# DSO_Front.net
KiCad netlist of a schematic drawn in Altium Designer
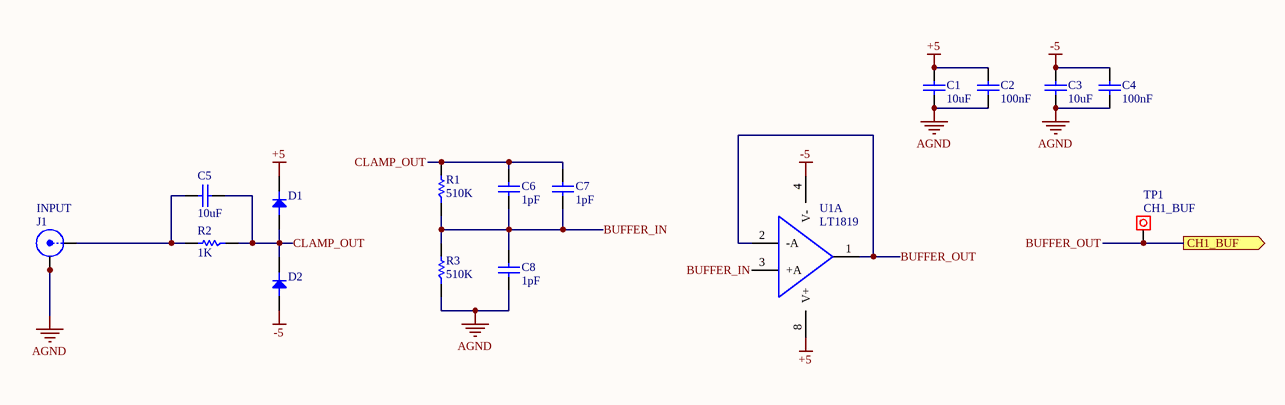
[diagram p0: DSO_Front.SchDoc]

(export (version "E")
  (design (tool "Eeschema 10.0.6"))
  (components
    (comp (ref "C1")
      (value "10uF")
      (footprint "0805C")
      (description "Capacitor")
      (fields (field (name "REVIEWED BY") "RM - 2018/08/05"))
      (libsource (lib "DSO") (part "C"))
    )
    (comp (ref "C2")
      (value "100nF")
      (footprint "0805C")
      (description "Capacitor")
      (fields (field (name "REVIEWED BY") "RM - 2018/08/05"))
      (libsource (lib "DSO") (part "C"))
    )
    (comp (ref "C3")
      (value "10uF")
      (footprint "0805C")
      (description "Capacitor")
      (fields (field (name "REVIEWED BY") "RM - 2018/08/05"))
      (libsource (lib "DSO") (part "C"))
    )
    (comp (ref "C4")
      (value "100nF")
      (footprint "0805C")
      (description "Capacitor")
      (fields (field (name "REVIEWED BY") "RM - 2018/08/05"))
      (libsource (lib "DSO") (part "C"))
    )
    (comp (ref "C5")
      (value "10uF")
      (footprint "0805C")
      (description "Capacitor")
      (fields (field (name "REVIEWED BY") "RM - 2018/08/05"))
      (libsource (lib "DSO") (part "C"))
    )
    (comp (ref "C6")
      (value "1pF")
      (footprint "0805C")
      (description "Capacitor")
      (fields (field (name "REVIEWED BY") "RM - 2018/08/05"))
      (libsource (lib "DSO") (part "C"))
    )
    (comp (ref "C7")
      (value "1pF")
      (footprint "0805C")
      (description "Capacitor")
      (fields (field (name "REVIEWED BY") "RM - 2018/08/05"))
      (libsource (lib "DSO") (part "C"))
    )
    (comp (ref "C8")
      (value "1pF")
      (footprint "0805C")
      (description "Capacitor")
      (fields (field (name "REVIEWED BY") "RM - 2018/08/05"))
      (libsource (lib "DSO") (part "C"))
    )
    (comp (ref "D1")
      (value "Diode")
      (footprint "SOD-123")
      (fields (field (name "REVIEWED BY") "RM - 2018/08/05"))
      (libsource (lib "DSO") (part "D"))
    )
    (comp (ref "D2")
      (value "Diode")
      (footprint "SOD-123")
      (fields (field (name "REVIEWED BY") "RM - 2018/08/05"))
      (libsource (lib "DSO") (part "D"))
    )
    (comp (ref "J1")
      (value "INPUT")
      (footprint "BNC_VERT")
      (description "BNC Straight")
      (fields (field (name "REVIEWED BY") "RM - 2018/08/05"))
      (libsource (lib "DSO") (part "BNC"))
    )
    (comp (ref "R1")
      (value "510K")
      (footprint "0805")
      (description "Resistor")
      (fields (field (name "REVIEWED BY") "RM - 2018/08/05"))
      (libsource (lib "DSO") (part "R"))
    )
    (comp (ref "R2")
      (value "1K")
      (footprint "0805")
      (description "Resistor")
      (fields (field (name "REVIEWED BY") "RM - 2018/08/05"))
      (libsource (lib "DSO") (part "R"))
    )
    (comp (ref "R3")
      (value "510K")
      (footprint "0805")
      (description "Resistor")
      (fields (field (name "REVIEWED BY") "RM - 2018/08/05"))
      (libsource (lib "DSO") (part "R"))
    )
    (comp (ref "TP1")
      (value "CH1_BUF")
      (footprint "Testpoin")
      (description "Pad")
      (libsource (lib "DSO") (part "Test Point"))
    )
    (comp (ref "U1")
      (value "LT1819")
      (footprint "SOIC-8")
      (description "OpAmp High Frequency Dual")
      (fields (field (name "REVIEWED BY") "RM - 2018/08/05"))
      (libsource (lib "DSO") (part "LT1819"))
    )
  )
  (nets
    (net (code "1") (name "+5") (class "Default")
      (node (ref "C1") (pin "1") (pinfunction "1_1") (pintype "passive"))
      (node (ref "C2") (pin "1") (pinfunction "1_1") (pintype "passive"))
      (node (ref "D1") (pin "K") (pinfunction "K_K") (pintype "passive"))
      (node (ref "U1") (pin "8") (pinfunction "V+_8") (pintype "passive"))
    )
    (net (code "2") (name "-5") (class "Default")
      (node (ref "C3") (pin "1") (pinfunction "1_1") (pintype "passive"))
      (node (ref "C4") (pin "1") (pinfunction "1_1") (pintype "passive"))
      (node (ref "D2") (pin "A") (pinfunction "A_A") (pintype "passive"))
      (node (ref "U1") (pin "4") (pinfunction "V-_4") (pintype "passive"))
    )
    (net (code "3") (name "/BUFFER_IN") (class "Default")
      (node (ref "C6") (pin "2") (pinfunction "2_2") (pintype "passive"))
      (node (ref "C7") (pin "2") (pinfunction "2_2") (pintype "passive"))
      (node (ref "C8") (pin "1") (pinfunction "1_1") (pintype "passive"))
      (node (ref "R1") (pin "1") (pintype "passive"))
      (node (ref "R3") (pin "2") (pintype "passive"))
      (node (ref "U1") (pin "3") (pinfunction "+A_3") (pintype "passive"))
    )
    (net (code "4") (name "/BUFFER_OUT") (class "Default")
      (node (ref "TP1") (pin "1") (pintype "passive"))
      (node (ref "U1") (pin "1") (pinfunction "OUTA_1") (pintype "passive"))
      (node (ref "U1") (pin "2") (pinfunction "-A_2") (pintype "passive"))
    )
    (net (code "5") (name "/CLAMP_OUT") (class "Default")
      (node (ref "C5") (pin "1") (pinfunction "1_1") (pintype "passive"))
      (node (ref "C6") (pin "1") (pinfunction "1_1") (pintype "passive"))
      (node (ref "C7") (pin "1") (pinfunction "1_1") (pintype "passive"))
      (node (ref "D1") (pin "A") (pinfunction "A_A") (pintype "passive"))
      (node (ref "D2") (pin "K") (pinfunction "K_K") (pintype "passive"))
      (node (ref "R1") (pin "2") (pintype "passive"))
      (node (ref "R2") (pin "1") (pintype "passive"))
    )
    (net (code "6") (name "AGND") (class "Default")
      (node (ref "C1") (pin "2") (pinfunction "2_2") (pintype "passive"))
      (node (ref "C2") (pin "2") (pinfunction "2_2") (pintype "passive"))
      (node (ref "C3") (pin "2") (pinfunction "2_2") (pintype "passive"))
      (node (ref "C4") (pin "2") (pinfunction "2_2") (pintype "passive"))
      (node (ref "C8") (pin "2") (pinfunction "2_2") (pintype "passive"))
      (node (ref "J1") (pin "2") (pinfunction "Y_2") (pintype "passive"))
      (node (ref "J1") (pin "3") (pinfunction "Y_3") (pintype "passive"))
      (node (ref "J1") (pin "4") (pinfunction "Y_4") (pintype "passive"))
      (node (ref "J1") (pin "5") (pinfunction "Y_5") (pintype "passive"))
      (node (ref "R3") (pin "1") (pintype "passive"))
    )
    (net (code "7") (name "Net-(J1-X)") (class "Default")
      (node (ref "C5") (pin "2") (pinfunction "2_2") (pintype "passive"))
      (node (ref "J1") (pin "1") (pinfunction "X_1") (pintype "passive"))
      (node (ref "R2") (pin "2") (pintype "passive"))
    )
  )
)
